# ProProject_PetCareSTM32_MiniSTM32_2024-0.net
KiCad netlist of a schematic drawn in EasyEDA Pro
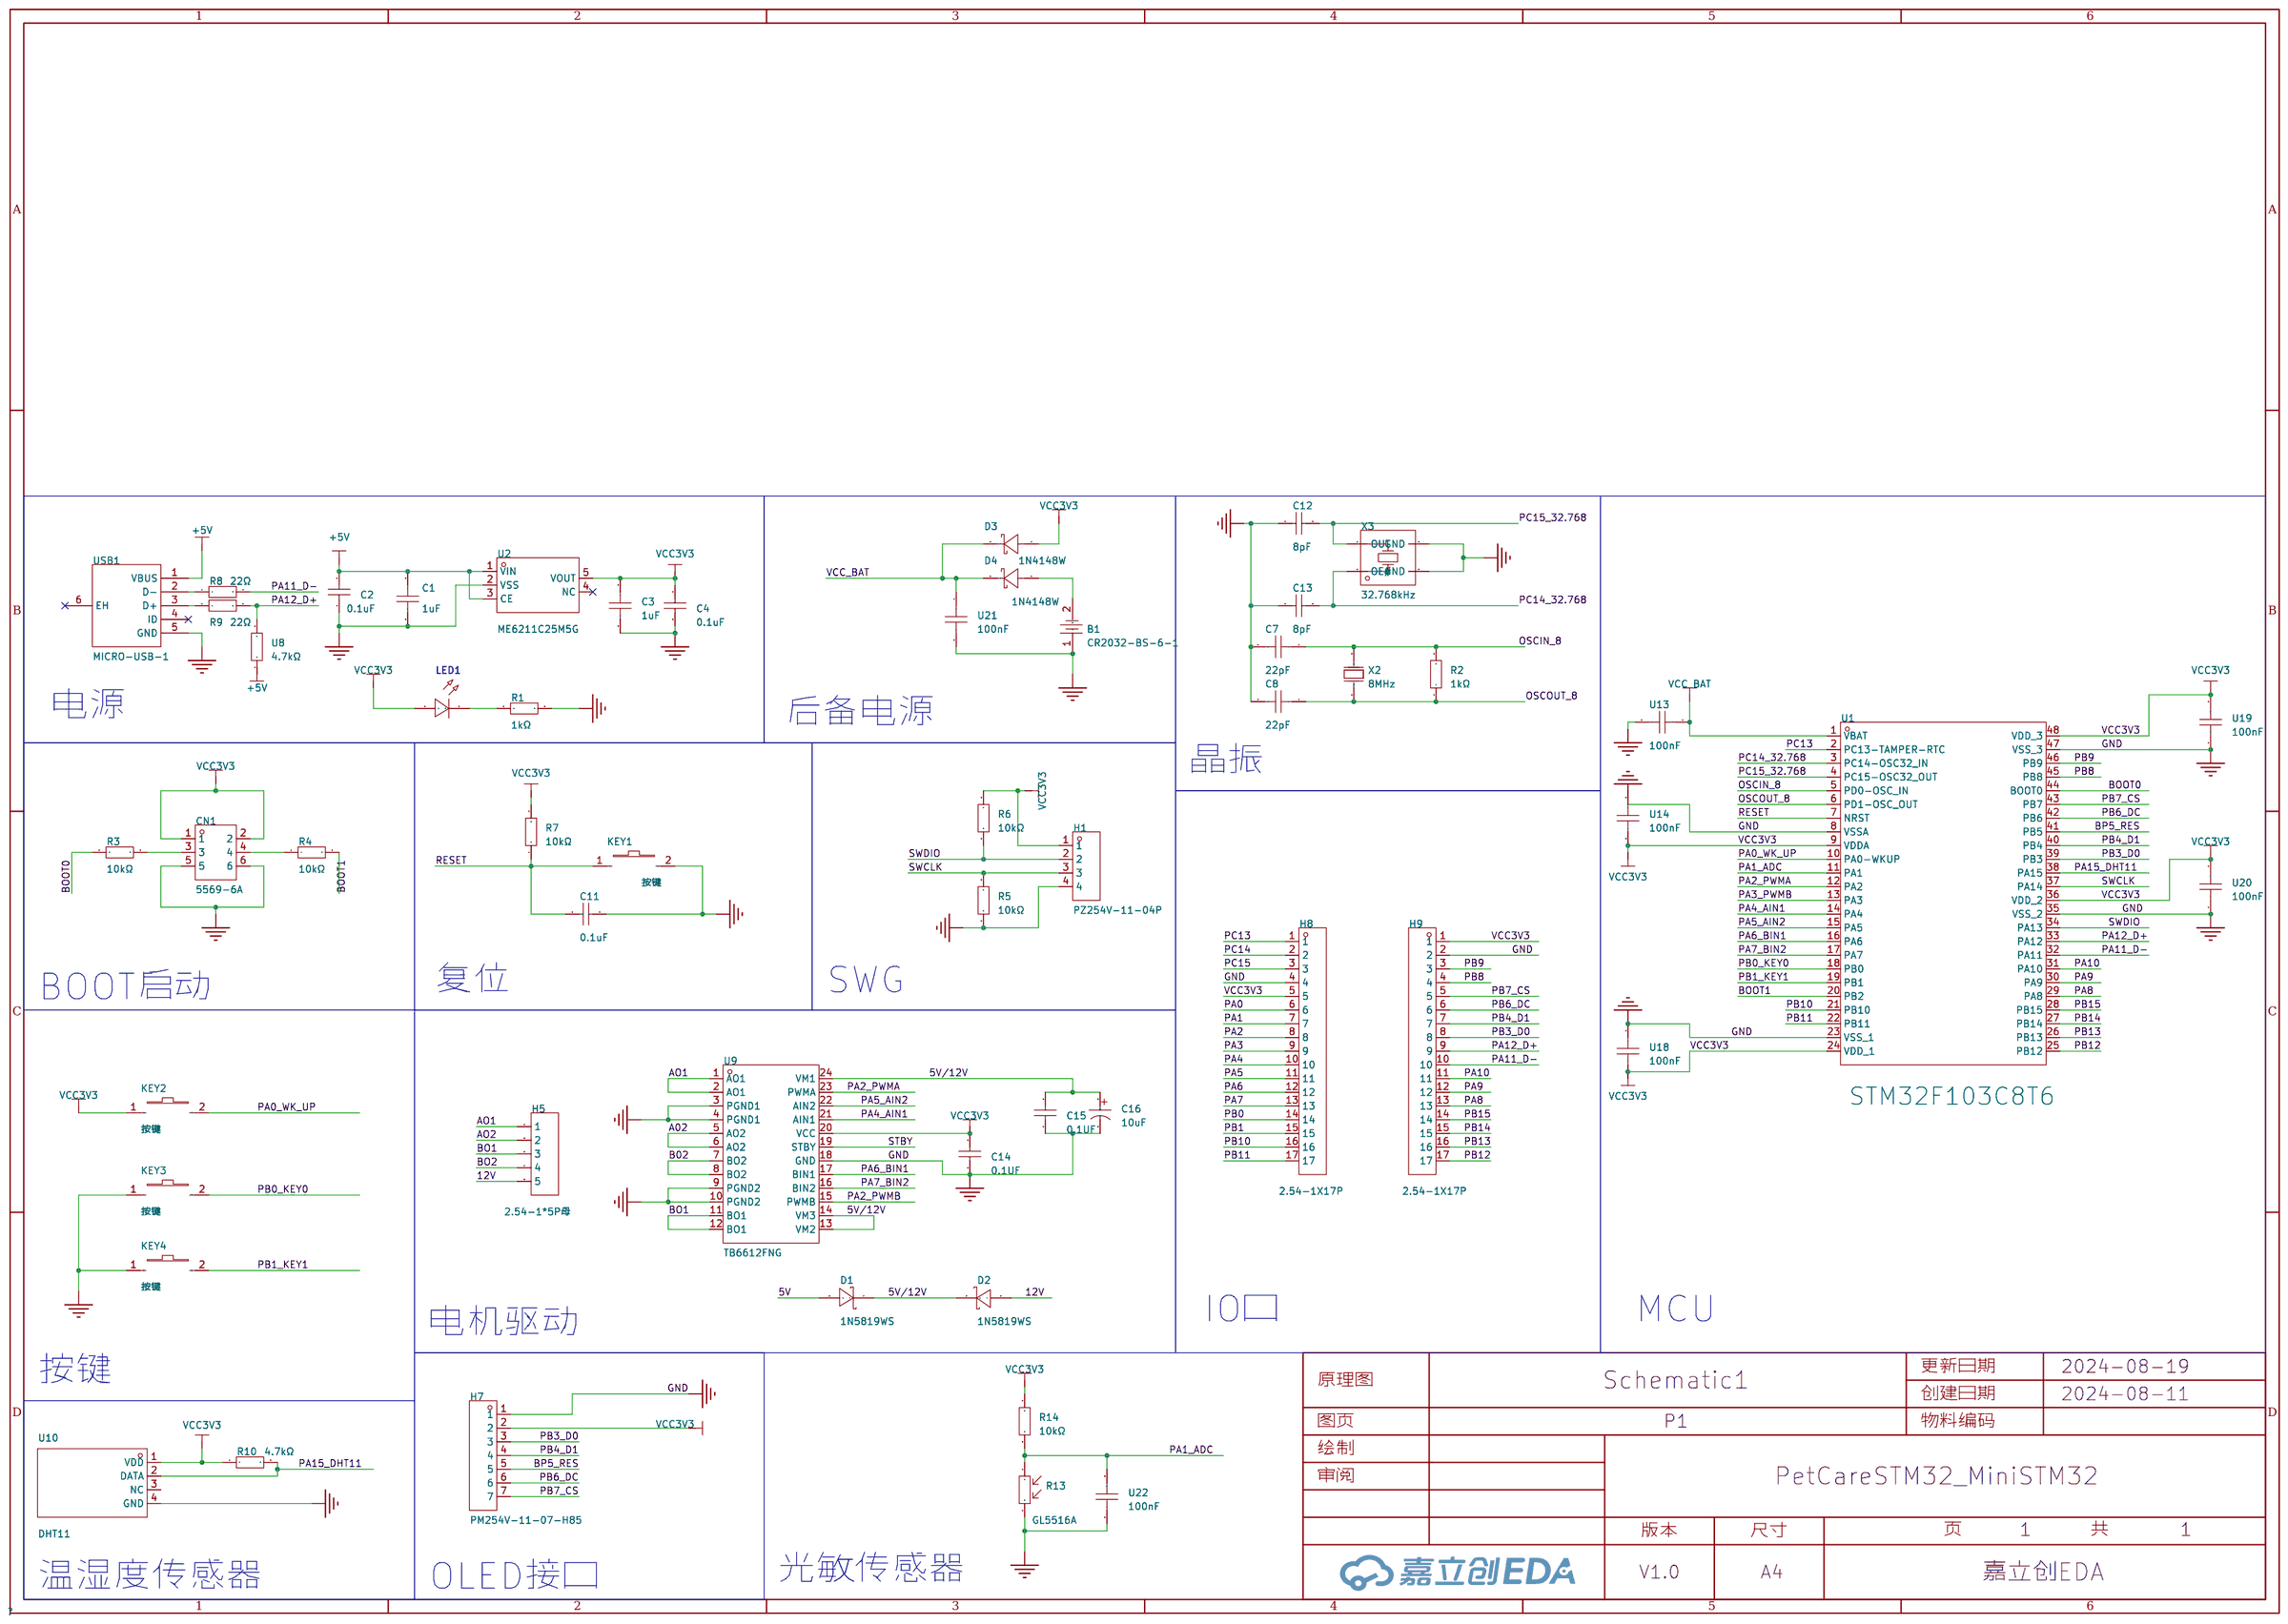
[diagram p0: schematic sheet]

(export (version "E")
  (design (tool "Eeschema 10.0.6"))
  (components
    (comp (ref "B1")
      (value "CR2032-BS-6-1")
      (footprint "easyedapro:BAT-TH_CR2032-BS-6-1")
      (description "连接器类型:电池底座;适用电池规格:CR2032;工作温度范围:-;")
      (fields (field (name "Manufacturer") "Q&J"))
      (libsource (lib "easyedapro") (part "CR2032-BS-6-1"))
    )
    (comp (ref "C1")
      (value "1uF")
      (footprint "easyedapro:C0603")
      (description "容值:1uF;精度:±10%;额定电压:50V;材质(温度系数):X5R;")
      (fields
        (field (name "Manufacturer Part") "CL10A105KB8NNNC")
        (field (name "Manufacturer") "SAMSUNG(三星)")
      )
      (libsource (lib "easyedapro") (part "CL10A105KB8NNNC"))
    )
    (comp (ref "C2")
      (value "0.1uF")
      (footprint "easyedapro:C0603")
      (libsource (lib "easyedapro") (part "CAPCER0.1UF16VX5R0603,CAPCER0.1UF25VX5R0603,CAPCER0.1UF16VX7R0603"))
    )
    (comp (ref "C3")
      (value "1uF")
      (footprint "easyedapro:C0603")
      (description "容值:1uF;精度:±10%;额定电压:50V;材质(温度系数):X5R;")
      (fields
        (field (name "Manufacturer Part") "CL10A105KB8NNNC")
        (field (name "Manufacturer") "SAMSUNG(三星)")
      )
      (libsource (lib "easyedapro") (part "CL10A105KB8NNNC"))
    )
    (comp (ref "C4")
      (value "0.1uF")
      (footprint "easyedapro:C0603")
      (libsource (lib "easyedapro") (part "CAPCER0.1UF16VX5R0603,CAPCER0.1UF25VX5R0603,CAPCER0.1UF16VX7R0603"))
    )
    (comp (ref "C7")
      (value "22pF")
      (footprint "easyedapro:C0603")
      (description "容值:22pF;精度:±5%;额定电压:50V;材质(温度系数):C0G;")
      (fields
        (field (name "Manufacturer Part") "CL10C220JB81PNC")
        (field (name "Manufacturer") "SAMSUNG(三星)")
      )
      (libsource (lib "easyedapro") (part "CL10C220JB81PNC"))
    )
    (comp (ref "C8")
      (value "22pF")
      (footprint "easyedapro:C0603")
      (description "容值:22pF;精度:±5%;额定电压:50V;材质(温度系数):C0G;")
      (fields
        (field (name "Manufacturer Part") "CL10C220JB81PNC")
        (field (name "Manufacturer") "SAMSUNG(三星)")
      )
      (libsource (lib "easyedapro") (part "CL10C220JB81PNC"))
    )
    (comp (ref "C11")
      (value "0.1uF")
      (footprint "easyedapro:C0603")
      (libsource (lib "easyedapro") (part "CAPCER0.1UF16VX5R0603,CAPCER0.1UF25VX5R0603,CAPCER0.1UF16VX7R0603"))
    )
    (comp (ref "C12")
      (value "8pF")
      (footprint "easyedapro:C0603")
      (description "容值:8pF;额定电压:50V;材质(温度系数):C0G;")
      (fields (field (name "Manufacturer Part") "0603CG8R0C500NT") (field (name "Manufacturer") "FH(风华)"))
      (libsource (lib "easyedapro") (part "0603CG8R0C500NT_C36508"))
    )
    (comp (ref "C13")
      (value "8pF")
      (footprint "easyedapro:C0603")
      (description "容值:8pF;额定电压:50V;材质(温度系数):C0G;")
      (fields (field (name "Manufacturer Part") "0603CG8R0C500NT") (field (name "Manufacturer") "FH(风华)"))
      (libsource (lib "easyedapro") (part "0603CG8R0C500NT_C36508"))
    )
    (comp (ref "C14")
      (value "0.1UF")
      (footprint "easyedapro:C0603")
      (libsource (lib "easyedapro") (part "CAPCER0.1UF16VX5R0603,CAPCER0.1UF25VX5R0603,CAPCER0.1UF16VX7R0603"))
    )
    (comp (ref "C15")
      (value "0.1UF")
      (footprint "easyedapro:C0603")
      (libsource (lib "easyedapro") (part "CAPCER0.1UF16VX5R0603,CAPCER0.1UF25VX5R0603,CAPCER0.1UF16VX7R0603"))
    )
    (comp (ref "C16")
      (value "10uF")
      (footprint "easyedapro:CAP-TH_BD5.0-P2.00-D0.8-FD")
      (description "容值:10uF;精度:±20%;额定电压:25V;")
      (fields (field (name "Manufacturer Part") "KF100M025C110A") (field (name "Manufacturer") "CapXon(丰宾)"))
      (libsource (lib "easyedapro") (part "KF100M025C110A"))
    )
    (comp (ref "CN1")
      (value "5569-6A")
      (footprint "easyedapro:CONN-TH_6P-P4.20_5569-6A-1")
      (libsource (lib "easyedapro") (part "5569-6A"))
    )
    (comp (ref "D1")
      (value "1N5819WS")
      (footprint "easyedapro:SOD-323_L1.8-W1.3-LS2.5-RD")
      (description "正向压降(Vf):600mV@1A;直流反向耐压(Vr):40V;平均整流电流(Io):1A;")
      (fields (field (name "Manufacturer") "Hottech(合科泰)"))
      (libsource (lib "easyedapro") (part "1N5819WS"))
    )
    (comp (ref "D2")
      (value "1N5819WS")
      (footprint "easyedapro:SOD-323_L1.8-W1.3-LS2.5-RD")
      (description "正向压降(Vf):600mV@1A;直流反向耐压(Vr):40V;平均整流电流(Io):1A;")
      (fields (field (name "Manufacturer") "Hottech(合科泰)"))
      (libsource (lib "easyedapro") (part "1N5819WS"))
    )
    (comp (ref "D3")
      (value "1N4148W")
      (footprint "easyedapro:SOD-123_L2.7-W1.6-LS3.7-FD")
      (description "二极管配置:独立式;正向压降(Vf):1.25V@150mA;直流反向耐压(Vr):100V;平均整流电流(Io):150mA;功率:400mW;反向恢复时间(trr):4ns;")
      (fields (field (name "Manufacturer") "宏迦橙"))
      (libsource (lib "easyedapro") (part "1N4148W_C7420318"))
    )
    (comp (ref "D4")
      (value "1N4148W")
      (footprint "easyedapro:SOD-123_L2.7-W1.6-LS3.7-FD")
      (description "二极管配置:独立式;正向压降(Vf):1.25V@150mA;直流反向耐压(Vr):100V;平均整流电流(Io):150mA;功率:400mW;反向恢复时间(trr):4ns;")
      (fields (field (name "Manufacturer") "宏迦橙"))
      (libsource (lib "easyedapro") (part "1N4148W_C7420318"))
    )
    (comp (ref "H1")
      (value "PZ254V-11-04P")
      (footprint "easyedapro:HDR-TH_4P-P2.54-V-M")
      (fields (field (name "Manufacturer") "XFCN(兴飞)"))
      (libsource (lib "easyedapro") (part "PZ254V-11-04P_C2691448"))
    )
    (comp (ref "H5")
      (value "2.54-1*5P母")
      (footprint "easyedapro:HDR-TH_5P-P2.54-V-F")
      (description "插孔结构:1x5P;间距:2.54mm;行距:-;安装类型:直插;排数:单排;总孔位数:5P;塑高:-;触头材质:-;触头镀层:-;")
      (fields (field (name "Manufacturer") "BOOMELE(博穆精密)"))
      (libsource (lib "easyedapro") (part "Header-Female-2.54_1x5"))
    )
    (comp (ref "H7")
      (value "PM254V-11-07-H85")
      (footprint "easyedapro:HDR-TH_7P-P2.54-V-F")
      (fields (field (name "Manufacturer") "XFCN(兴飞)"))
      (libsource (lib "easyedapro") (part "PM254V-11-07-H85"))
    )
    (comp (ref "H8")
      (value "2.54-1X17P")
      (footprint "easyedapro:HDR-TH_17P-P2.54-V-M")
      (fields (field (name "Manufacturer") "kinghelm(金航标)"))
      (libsource (lib "easyedapro") (part "KH-2.54PH180-1X17P-L11.5"))
    )
    (comp (ref "H9")
      (value "2.54-1X17P")
      (footprint "easyedapro:HDR-TH_17P-P2.54-V-M")
      (fields (field (name "Manufacturer") "kinghelm(金航标)"))
      (libsource (lib "easyedapro") (part "KH-2.54PH180-1X17P-L11.5"))
    )
    (comp (ref "KEY1")
      (value "按键")
      (footprint "easyedapro:SW-SMD_L6.0-W3.6-LS8.0")
      (libsource (lib "easyedapro") (part "3x6x2.5mm"))
    )
    (comp (ref "KEY2")
      (value "按键")
      (footprint "easyedapro:SW-SMD_L6.0-W3.6-LS8.0")
      (libsource (lib "easyedapro") (part "3x6x2.5mm"))
    )
    (comp (ref "KEY3")
      (value "按键")
      (footprint "easyedapro:SW-SMD_L6.0-W3.6-LS8.0")
      (libsource (lib "easyedapro") (part "3x6x2.5mm"))
    )
    (comp (ref "KEY4")
      (value "按键")
      (footprint "easyedapro:SW-SMD_L6.0-W3.6-LS8.0")
      (libsource (lib "easyedapro") (part "3x6x2.5mm"))
    )
    (comp (ref "LED1")
      (value "~")
      (footprint "easyedapro:LED_0805")
      (libsource (lib "easyedapro") (part "LED_B"))
    )
    (comp (ref "R1")
      (value "1kΩ")
      (footprint "easyedapro:R0603")
      (description "电阻类型:厚膜电阻;阻值:1kΩ;精度:±1%;功率:100mW;最大工作电压:75V;温度系数:±100ppm/°C;")
      (fields (field (name "Manufacturer Part") "RC0603FR-071KL") (field (name "Manufacturer") "YAGEO(国巨)"))
      (libsource (lib "easyedapro") (part "RC0603FR-071KL"))
    )
    (comp (ref "R2")
      (value "1kΩ")
      (footprint "easyedapro:R0603")
      (description "电阻类型:厚膜电阻;阻值:1kΩ;精度:±0.5%;功率:100mW;最大工作电压:75V;温度系数:±100ppm/°C;")
      (fields
        (field (name "Manufacturer Part") "0603WAD1001T5E")
        (field (name "Manufacturer") "UNI-ROYAL(厚声)")
      )
      (libsource (lib "easyedapro") (part "0603WAD1001T5E"))
    )
    (comp (ref "R3")
      (value "10kΩ")
      (footprint "easyedapro:R0603")
      (description "电阻类型:厚膜电阻;阻值:10kΩ;精度:±1%;功率:100mW;最大工作电压:75V;温度系数:±100ppm/°C;")
      (fields
        (field (name "Manufacturer Part") "0603WAF1002T5E")
        (field (name "Manufacturer") "UNI-ROYAL(厚声)")
      )
      (libsource (lib "easyedapro") (part "0603WAF1002T5E"))
    )
    (comp (ref "R4")
      (value "10kΩ")
      (footprint "easyedapro:R0603")
      (description "电阻类型:厚膜电阻;阻值:10kΩ;精度:±1%;功率:100mW;最大工作电压:75V;温度系数:±100ppm/°C;")
      (fields
        (field (name "Manufacturer Part") "0603WAF1002T5E")
        (field (name "Manufacturer") "UNI-ROYAL(厚声)")
      )
      (libsource (lib "easyedapro") (part "0603WAF1002T5E"))
    )
    (comp (ref "R5")
      (value "10kΩ")
      (footprint "easyedapro:R0603")
      (description "电阻类型:厚膜电阻;阻值:10kΩ;精度:±1%;功率:100mW;最大工作电压:75V;温度系数:±100ppm/°C;")
      (fields
        (field (name "Manufacturer Part") "0603WAF1002T5E")
        (field (name "Manufacturer") "UNI-ROYAL(厚声)")
      )
      (libsource (lib "easyedapro") (part "0603WAF1002T5E"))
    )
    (comp (ref "R6")
      (value "10kΩ")
      (footprint "easyedapro:R0603")
      (description "电阻类型:厚膜电阻;阻值:10kΩ;精度:±1%;功率:100mW;最大工作电压:75V;温度系数:±100ppm/°C;")
      (fields
        (field (name "Manufacturer Part") "0603WAF1002T5E")
        (field (name "Manufacturer") "UNI-ROYAL(厚声)")
      )
      (libsource (lib "easyedapro") (part "0603WAF1002T5E"))
    )
    (comp (ref "R7")
      (value "10kΩ")
      (footprint "easyedapro:R0603")
      (description "电阻类型:厚膜电阻;阻值:10kΩ;精度:±1%;功率:100mW;最大工作电压:75V;温度系数:±100ppm/°C;")
      (fields
        (field (name "Manufacturer Part") "0603WAF1002T5E")
        (field (name "Manufacturer") "UNI-ROYAL(厚声)")
      )
      (libsource (lib "easyedapro") (part "0603WAF1002T5E"))
    )
    (comp (ref "R8")
      (value "22Ω")
      (footprint "easyedapro:R0805")
      (description "电阻类型:薄膜电阻;阻值:22Ω;精度:±1%;功率:250mW;最大工作电压:150V;温度系数:±25ppm/°C;")
      (fields
        (field (name "Manufacturer Part") "TC0525F220JT5E")
        (field (name "Manufacturer") "UNI-ROYAL(厚声)")
      )
      (libsource (lib "easyedapro") (part "TC0525F220JT5E"))
    )
    (comp (ref "R9")
      (value "22Ω")
      (footprint "easyedapro:R0805")
      (description "电阻类型:薄膜电阻;阻值:22Ω;精度:±1%;功率:250mW;最大工作电压:150V;温度系数:±25ppm/°C;")
      (fields
        (field (name "Manufacturer Part") "TC0525F220JT5E")
        (field (name "Manufacturer") "UNI-ROYAL(厚声)")
      )
      (libsource (lib "easyedapro") (part "TC0525F220JT5E"))
    )
    (comp (ref "R10")
      (value "4.7kΩ")
      (footprint "easyedapro:R1206")
      (description "电阻类型:厚膜电阻;阻值:4.7kΩ;精度:±1%;功率:250mW;最大工作电压:200V;温度系数:±100ppm/°C;")
      (fields
        (field (name "Manufacturer Part") "1206W4F4701T5E")
        (field (name "Manufacturer") "UNI-ROYAL(厚声)")
      )
      (libsource (lib "easyedapro") (part "1206W4F4701T5E"))
    )
    (comp (ref "R13")
      (value "GL5516A")
      (footprint "easyedapro:RES-TH_L5.1-W4.3-P3.40_GL55")
      (description "暗电阻:200kΩ;亮电阻 @ 10Lux:5kΩ~10kΩ;光谱峰值(波长):540nm;")
      (fields (field (name "Manufacturer") "JCHL(晶创和立)"))
      (libsource (lib "easyedapro") (part "GL5516A(5-10K)"))
    )
    (comp (ref "R14")
      (value "10kΩ")
      (footprint "easyedapro:R0603")
      (description "电阻类型:厚膜电阻;阻值:10kΩ;精度:±1%;功率:100mW;最大工作电压:75V;温度系数:±100ppm/°C;")
      (fields
        (field (name "Manufacturer Part") "0603WAF1002T5E")
        (field (name "Manufacturer") "UNI-ROYAL(厚声)")
      )
      (libsource (lib "easyedapro") (part "0603WAF1002T5E"))
    )
    (comp (ref "U1")
      (value "STM32F103C8T6")
      (footprint "easyedapro:LQFP-48_L7.0-W7.0-P0.50-LS9.0-BL")
      (description "CPU内核:ARM-M3;程序存储容量:64KB;RAM总容量:20KB;GPIO端口数量:37;工作电压范围:2V~3.6V;CPU最大主频:72MHz;程序存储器类型:FLASH;")
      (fields (field (name "Manufacturer") "ST(意法半导体)"))
      (libsource (lib "easyedapro") (part "STM32F103C8T6"))
    )
    (comp (ref "U2")
      (value "ME6211C25M5G")
      (footprint "easyedapro:SOT-23-5_L2.9-W1.7-P0.95-LS2.8-BL")
      (fields (field (name "Manufacturer") "MICRONE(南京微盟)"))
      (libsource (lib "easyedapro") (part "ME6211C25M5G"))
    )
    (comp (ref "U8")
      (value "4.7kΩ")
      (footprint "easyedapro:R0603")
      (description "电阻类型:薄膜电阻;阻值:4.7kΩ;精度:±1%;功率:100mW;最大工作电压:75V;温度系数:±50ppm/°C;")
      (fields (field (name "Manufacturer Part") "AR03FTDX4701A") (field (name "Manufacturer") "Viking(光颉)"))
      (libsource (lib "easyedapro") (part "AR03FTDX4701A"))
    )
    (comp (ref "U9")
      (value "TB6612FNG")
      (footprint "easyedapro:SSOP-24_L8.4-W5.8-P0.65-LS7.8-BL")
      (description "双直流电机驱动器集成电路")
      (fields (field (name "Manufacturer") "TOSHIBA(东芝)"))
      (libsource (lib "easyedapro") (part "TB6612FNG(O,C,8,EL"))
    )
    (comp (ref "U10")
      (value "DHT11")
      (footprint "easyedapro:SENSOR-TH_DHT11")
      (description "新款电容式数字温湿度传感器,老款已停产16.1x12.6x5.8mm")
      (fields (field (name "Manufacturer") "广州奥松"))
      (libsource (lib "easyedapro") (part "DHT11"))
    )
    (comp (ref "U13")
      (value "100nF")
      (footprint "easyedapro:C0603")
      (description "容值:100nF;精度:±10%;额定电压:50V;材质(温度系数):X7R;")
      (fields
        (field (name "Manufacturer Part") "CGA0603X7R104K500JT")
        (field (name "Manufacturer") "HRE(芯声)")
      )
      (libsource (lib "easyedapro") (part "CGA0603X7R104K500JT"))
    )
    (comp (ref "U14")
      (value "100nF")
      (footprint "easyedapro:C0603")
      (description "容值:100nF;精度:±10%;额定电压:50V;材质(温度系数):X7R;")
      (fields
        (field (name "Manufacturer Part") "CGA0603X7R104K500JT")
        (field (name "Manufacturer") "HRE(芯声)")
      )
      (libsource (lib "easyedapro") (part "CGA0603X7R104K500JT"))
    )
    (comp (ref "U18")
      (value "100nF")
      (footprint "easyedapro:C0603")
      (description "容值:100nF;精度:±10%;额定电压:50V;材质(温度系数):X7R;")
      (fields
        (field (name "Manufacturer Part") "CGA0603X7R104K500JT")
        (field (name "Manufacturer") "HRE(芯声)")
      )
      (libsource (lib "easyedapro") (part "CGA0603X7R104K500JT"))
    )
    (comp (ref "U19")
      (value "100nF")
      (footprint "easyedapro:C0603")
      (description "容值:100nF;精度:±10%;额定电压:50V;材质(温度系数):X7R;")
      (fields
        (field (name "Manufacturer Part") "CGA0603X7R104K500JT")
        (field (name "Manufacturer") "HRE(芯声)")
      )
      (libsource (lib "easyedapro") (part "CGA0603X7R104K500JT"))
    )
    (comp (ref "U20")
      (value "100nF")
      (footprint "easyedapro:C0603")
      (description "容值:100nF;精度:±10%;额定电压:50V;材质(温度系数):X7R;")
      (fields
        (field (name "Manufacturer Part") "CGA0603X7R104K500JT")
        (field (name "Manufacturer") "HRE(芯声)")
      )
      (libsource (lib "easyedapro") (part "CGA0603X7R104K500JT"))
    )
    (comp (ref "U21")
      (value "100nF")
      (footprint "easyedapro:C0603")
      (description "容值:100nF;精度:±10%;额定电压:50V;材质(温度系数):X7R;")
      (fields
        (field (name "Manufacturer Part") "CGA0603X7R104K500JT")
        (field (name "Manufacturer") "HRE(芯声)")
      )
      (libsource (lib "easyedapro") (part "CGA0603X7R104K500JT"))
    )
    (comp (ref "U22")
      (value "100nF")
      (footprint "easyedapro:C0603")
      (description "容值:100nF;精度:±10%;额定电压:50V;材质(温度系数):X7R;")
      (fields
        (field (name "Manufacturer Part") "CGA0603X7R104K500JT")
        (field (name "Manufacturer") "HRE(芯声)")
      )
      (libsource (lib "easyedapro") (part "CGA0603X7R104K500JT"))
    )
    (comp (ref "USB1")
      (value "MICRO-USB-1")
      (footprint "easyedapro:MICRO-USB-SMD_C9900008946")
      (libsource (lib "easyedapro") (part "MICRO-USB-1"))
    )
    (comp (ref "X2")
      (value "8MHz")
      (footprint "easyedapro:OSC-SMD_L5.0-W3.2")
      (description "晶振类型:贴片晶振;频率:8MHz;常温频差:±20ppm;外接负载电容:18pF;频率稳定度(全温):±30ppm;")
      (fields
        (field (name "Manufacturer Part") "ABM3-8.000MHZ-D2Y-T")
        (field (name "Manufacturer") "ABRACON")
      )
      (libsource (lib "easyedapro") (part "ABM3-8.000MHZ-D2Y-T"))
    )
    (comp (ref "X3")
      (value "32.768kHz")
      (footprint "easyedapro:CRYSTAL-SMD_4P-L8.0-W3.8-BL")
      (description "晶振类型:-;频率:32.768kHz;常温频差:±20ppm;外接负载电容:12.5pF;频率稳定度(全温):-;")
      (fields (field (name "Manufacturer Part") "ABS25-32.768KHZ-T") (field (name "Manufacturer") "ABRACON"))
      (libsource (lib "easyedapro") (part "ABS25-32.768KHZ-T"))
    )
  )
  (nets
    (net (code "1") (name "+5V") (class "Default")
      (node (ref "C1") (pin "2") (pinfunction "2_2") (pintype "unspecified"))
      (node (ref "C2") (pin "2") (pinfunction "2_2") (pintype "input"))
      (node (ref "U2") (pin "1") (pinfunction "VIN_1") (pintype "unspecified"))
      (node (ref "U2") (pin "3") (pinfunction "CE_3") (pintype "unspecified"))
      (node (ref "U8") (pin "1") (pinfunction "1_1") (pintype "unspecified"))
      (node (ref "USB1") (pin "1") (pinfunction "VBUS_1") (pintype "input"))
    )
    (net (code "2") (name "/5V") (class "Default")
      (node (ref "D1") (pin "2") (pinfunction "A_2") (pintype "unspecified"))
    )
    (net (code "3") (name "/5V{slash}12V") (class "Default")
      (node (ref "C15") (pin "2") (pinfunction "2_2") (pintype "input"))
      (node (ref "C16") (pin "1") (pinfunction "1_1") (pintype "input"))
      (node (ref "D1") (pin "1") (pinfunction "K_1") (pintype "unspecified"))
      (node (ref "D2") (pin "1") (pinfunction "K_1") (pintype "unspecified"))
      (node (ref "U9") (pin "13") (pinfunction "VM2_13") (pintype "unspecified"))
      (node (ref "U9") (pin "14") (pinfunction "VM3_14") (pintype "unspecified"))
      (node (ref "U9") (pin "24") (pinfunction "VM1_24") (pintype "unspecified"))
    )
    (net (code "4") (name "/12V") (class "Default")
      (node (ref "D2") (pin "2") (pinfunction "A_2") (pintype "unspecified"))
      (node (ref "H5") (pin "5") (pinfunction "5_5") (pintype "input"))
    )
    (net (code "5") (name "/A02") (class "Default")
      (node (ref "U9") (pin "5") (pinfunction "AO2_5") (pintype "unspecified"))
      (node (ref "U9") (pin "6") (pinfunction "AO2_6") (pintype "unspecified"))
    )
    (net (code "6") (name "/AO1") (class "Default")
      (node (ref "H5") (pin "1") (pinfunction "1_1") (pintype "input"))
      (node (ref "U9") (pin "1") (pinfunction "AO1_1") (pintype "unspecified"))
      (node (ref "U9") (pin "2") (pinfunction "AO1_2") (pintype "unspecified"))
    )
    (net (code "7") (name "/AO2") (class "Default")
      (node (ref "H5") (pin "2") (pinfunction "2_2") (pintype "input"))
    )
    (net (code "8") (name "/B02") (class "Default")
      (node (ref "U9") (pin "7") (pinfunction "BO2_7") (pintype "unspecified"))
      (node (ref "U9") (pin "8") (pinfunction "BO2_8") (pintype "unspecified"))
    )
    (net (code "9") (name "/BO1") (class "Default")
      (node (ref "H5") (pin "3") (pinfunction "3_3") (pintype "input"))
      (node (ref "U9") (pin "11") (pinfunction "BO1_11") (pintype "unspecified"))
      (node (ref "U9") (pin "12") (pinfunction "BO1_12") (pintype "unspecified"))
    )
    (net (code "10") (name "/BO2") (class "Default")
      (node (ref "H5") (pin "4") (pinfunction "4_4") (pintype "input"))
    )
    (net (code "11") (name "/BOOT0") (class "Default")
      (node (ref "R3") (pin "1") (pinfunction "1_1") (pintype "input"))
      (node (ref "U1") (pin "44") (pinfunction "BOOT0_44") (pintype "unspecified"))
    )
    (net (code "12") (name "/BOOT1") (class "Default")
      (node (ref "R4") (pin "2") (pinfunction "2_2") (pintype "input"))
      (node (ref "U1") (pin "20") (pinfunction "PB2_20") (pintype "unspecified"))
    )
    (net (code "13") (name "/BP5_RES") (class "Default")
      (node (ref "H7") (pin "5") (pinfunction "5_5") (pintype "unspecified"))
      (node (ref "U1") (pin "41") (pinfunction "PB5_41") (pintype "unspecified"))
    )
    (net (code "14") (name "/OSCIN_8") (class "Default")
      (node (ref "C7") (pin "1") (pinfunction "1_1") (pintype "unspecified"))
      (node (ref "R2") (pin "2") (pinfunction "2_2") (pintype "input"))
      (node (ref "U1") (pin "5") (pinfunction "PD0-OSC_IN_5") (pintype "unspecified"))
      (node (ref "X2") (pin "2") (pinfunction "OSC2_2") (pintype "input"))
    )
    (net (code "15") (name "/OSCOUT_8") (class "Default")
      (node (ref "C8") (pin "1") (pinfunction "1_1") (pintype "unspecified"))
      (node (ref "R2") (pin "1") (pinfunction "1_1") (pintype "input"))
      (node (ref "U1") (pin "6") (pinfunction "PD1-OSC_OUT_6") (pintype "unspecified"))
      (node (ref "X2") (pin "1") (pinfunction "OSC1_1") (pintype "input"))
    )
    (net (code "16") (name "/PA0") (class "Default")
      (node (ref "H8") (pin "6") (pinfunction "6_6") (pintype "unspecified"))
    )
    (net (code "17") (name "/PA0_WK_UP") (class "Default")
      (node (ref "KEY2") (pin "2") (pinfunction "2_2") (pintype "input"))
      (node (ref "U1") (pin "10") (pinfunction "PA0-WKUP_10") (pintype "unspecified"))
    )
    (net (code "18") (name "/PA1") (class "Default")
      (node (ref "H8") (pin "7") (pinfunction "7_7") (pintype "unspecified"))
    )
    (net (code "19") (name "/PA1_ADC") (class "Default")
      (node (ref "R13") (pin "1") (pinfunction "1_1") (pintype "input"))
      (node (ref "R14") (pin "1") (pinfunction "1_1") (pintype "input"))
      (node (ref "U1") (pin "11") (pinfunction "PA1_11") (pintype "unspecified"))
      (node (ref "U22") (pin "2") (pinfunction "2_2") (pintype "unspecified"))
    )
    (net (code "20") (name "/PA2") (class "Default")
      (node (ref "H8") (pin "8") (pinfunction "8_8") (pintype "unspecified"))
    )
    (net (code "21") (name "/PA2_PWMA") (class "Default")
      (node (ref "U1") (pin "12") (pinfunction "PA2_12") (pintype "unspecified"))
      (node (ref "U9") (pin "23") (pinfunction "PWMA_23") (pintype "unspecified"))
    )
    (net (code "22") (name "/PA2_PWMB") (class "Default")
      (node (ref "U9") (pin "15") (pinfunction "PWMB_15") (pintype "unspecified"))
    )
    (net (code "23") (name "/PA3") (class "Default")
      (node (ref "H8") (pin "9") (pinfunction "9_9") (pintype "unspecified"))
    )
    (net (code "24") (name "/PA3_PWMB") (class "Default")
      (node (ref "U1") (pin "13") (pinfunction "PA3_13") (pintype "unspecified"))
    )
    (net (code "25") (name "/PA4") (class "Default")
      (node (ref "H8") (pin "10") (pinfunction "10_10") (pintype "unspecified"))
    )
    (net (code "26") (name "/PA4_AIN1") (class "Default")
      (node (ref "U1") (pin "14") (pinfunction "PA4_14") (pintype "unspecified"))
      (node (ref "U9") (pin "21") (pinfunction "AIN1_21") (pintype "unspecified"))
    )
    (net (code "27") (name "/PA5") (class "Default")
      (node (ref "H8") (pin "11") (pinfunction "11_11") (pintype "unspecified"))
    )
    (net (code "28") (name "/PA5_AIN2") (class "Default")
      (node (ref "U1") (pin "15") (pinfunction "PA5_15") (pintype "unspecified"))
      (node (ref "U9") (pin "22") (pinfunction "AIN2_22") (pintype "unspecified"))
    )
    (net (code "29") (name "/PA6") (class "Default")
      (node (ref "H8") (pin "12") (pinfunction "12_12") (pintype "unspecified"))
    )
    (net (code "30") (name "/PA6_BIN1") (class "Default")
      (node (ref "U1") (pin "16") (pinfunction "PA6_16") (pintype "unspecified"))
      (node (ref "U9") (pin "17") (pinfunction "BIN1_17") (pintype "unspecified"))
    )
    (net (code "31") (name "/PA7") (class "Default")
      (node (ref "H8") (pin "13") (pinfunction "13_13") (pintype "unspecified"))
    )
    (net (code "32") (name "/PA7_BIN2") (class "Default")
      (node (ref "U1") (pin "17") (pinfunction "PA7_17") (pintype "unspecified"))
      (node (ref "U9") (pin "16") (pinfunction "BIN2_16") (pintype "unspecified"))
    )
    (net (code "33") (name "/PA8") (class "Default")
      (node (ref "H9") (pin "13") (pinfunction "13_13") (pintype "unspecified"))
      (node (ref "U1") (pin "29") (pinfunction "PA8_29") (pintype "unspecified"))
    )
    (net (code "34") (name "/PA9") (class "Default")
      (node (ref "H9") (pin "12") (pinfunction "12_12") (pintype "unspecified"))
      (node (ref "U1") (pin "30") (pinfunction "PA9_30") (pintype "unspecified"))
    )
    (net (code "35") (name "/PA10") (class "Default")
      (node (ref "H9") (pin "11") (pinfunction "11_11") (pintype "unspecified"))
      (node (ref "U1") (pin "31") (pinfunction "PA10_31") (pintype "unspecified"))
    )
    (net (code "36") (name "/PA11_D-") (class "Default")
      (node (ref "H9") (pin "10") (pinfunction "10_10") (pintype "unspecified"))
      (node (ref "R8") (pin "2") (pinfunction "2_2") (pintype "input"))
      (node (ref "U1") (pin "32") (pinfunction "PA11_32") (pintype "unspecified"))
    )
    (net (code "37") (name "/PA12_D+") (class "Default")
      (node (ref "H9") (pin "9") (pinfunction "9_9") (pintype "unspecified"))
      (node (ref "R9") (pin "2") (pinfunction "2_2") (pintype "input"))
      (node (ref "U1") (pin "33") (pinfunction "PA12_33") (pintype "unspecified"))
      (node (ref "U8") (pin "2") (pinfunction "2_2") (pintype "unspecified"))
    )
    (net (code "38") (name "/PA15_DHT11") (class "Default")
      (node (ref "R10") (pin "2") (pinfunction "2_2") (pintype "input"))
      (node (ref "U1") (pin "38") (pinfunction "PA15_38") (pintype "unspecified"))
      (node (ref "U10") (pin "2") (pinfunction "DATA_2") (pintype "unspecified"))
    )
    (net (code "39") (name "/PB0") (class "Default")
      (node (ref "H8") (pin "14") (pinfunction "14_14") (pintype "unspecified"))
    )
    (net (code "40") (name "/PB0_KEY0") (class "Default")
      (node (ref "KEY3") (pin "2") (pinfunction "2_2") (pintype "input"))
      (node (ref "U1") (pin "18") (pinfunction "PB0_18") (pintype "unspecified"))
    )
    (net (code "41") (name "/PB1") (class "Default")
      (node (ref "H8") (pin "15") (pinfunction "15_15") (pintype "unspecified"))
    )
    (net (code "42") (name "/PB1_KEY1") (class "Default")
      (node (ref "KEY4") (pin "2") (pinfunction "2_2") (pintype "input"))
      (node (ref "U1") (pin "19") (pinfunction "PB1_19") (pintype "unspecified"))
    )
    (net (code "43") (name "/PB3_D0") (class "Default")
      (node (ref "H7") (pin "3") (pinfunction "3_3") (pintype "unspecified"))
      (node (ref "H9") (pin "8") (pinfunction "8_8") (pintype "unspecified"))
      (node (ref "U1") (pin "39") (pinfunction "PB3_39") (pintype "unspecified"))
    )
    (net (code "44") (name "/PB4_D1") (class "Default")
      (node (ref "H7") (pin "4") (pinfunction "4_4") (pintype "unspecified"))
      (node (ref "H9") (pin "7") (pinfunction "7_7") (pintype "unspecified"))
      (node (ref "U1") (pin "40") (pinfunction "PB4_40") (pintype "unspecified"))
    )
    (net (code "45") (name "/PB6_DC") (class "Default")
      (node (ref "H7") (pin "6") (pinfunction "6_6") (pintype "unspecified"))
      (node (ref "H9") (pin "6") (pinfunction "6_6") (pintype "unspecified"))
      (node (ref "U1") (pin "42") (pinfunction "PB6_42") (pintype "unspecified"))
    )
    (net (code "46") (name "/PB7_CS") (class "Default")
      (node (ref "H7") (pin "7") (pinfunction "7_7") (pintype "unspecified"))
      (node (ref "H9") (pin "5") (pinfunction "5_5") (pintype "unspecified"))
      (node (ref "U1") (pin "43") (pinfunction "PB7_43") (pintype "unspecified"))
    )
    (net (code "47") (name "/PB8") (class "Default")
      (node (ref "H9") (pin "4") (pinfunction "4_4") (pintype "unspecified"))
      (node (ref "U1") (pin "45") (pinfunction "PB8_45") (pintype "unspecified"))
    )
    (net (code "48") (name "/PB9") (class "Default")
      (node (ref "H9") (pin "3") (pinfunction "3_3") (pintype "unspecified"))
      (node (ref "U1") (pin "46") (pinfunction "PB9_46") (pintype "unspecified"))
    )
    (net (code "49") (name "/PB10") (class "Default")
      (node (ref "H8") (pin "16") (pinfunction "16_16") (pintype "unspecified"))
      (node (ref "U1") (pin "21") (pinfunction "PB10_21") (pintype "unspecified"))
    )
    (net (code "50") (name "/PB11") (class "Default")
      (node (ref "H8") (pin "17") (pinfunction "17_17") (pintype "unspecified"))
      (node (ref "U1") (pin "22") (pinfunction "PB11_22") (pintype "unspecified"))
    )
    (net (code "51") (name "/PB12") (class "Default")
      (node (ref "H9") (pin "17") (pinfunction "17_17") (pintype "unspecified"))
      (node (ref "U1") (pin "25") (pinfunction "PB12_25") (pintype "unspecified"))
    )
    (net (code "52") (name "/PB13") (class "Default")
      (node (ref "H9") (pin "16") (pinfunction "16_16") (pintype "unspecified"))
      (node (ref "U1") (pin "26") (pinfunction "PB13_26") (pintype "unspecified"))
    )
    (net (code "53") (name "/PB14") (class "Default")
      (node (ref "H9") (pin "15") (pinfunction "15_15") (pintype "unspecified"))
      (node (ref "U1") (pin "27") (pinfunction "PB14_27") (pintype "unspecified"))
    )
    (net (code "54") (name "/PB15") (class "Default")
      (node (ref "H9") (pin "14") (pinfunction "14_14") (pintype "unspecified"))
      (node (ref "U1") (pin "28") (pinfunction "PB15_28") (pintype "unspecified"))
    )
    (net (code "55") (name "/PC13") (class "Default")
      (node (ref "H8") (pin "1") (pinfunction "1_1") (pintype "unspecified"))
      (node (ref "U1") (pin "2") (pinfunction "PC13-TAMPER-RTC_2") (pintype "unspecified"))
    )
    (net (code "56") (name "/PC14") (class "Default")
      (node (ref "H8") (pin "2") (pinfunction "2_2") (pintype "unspecified"))
    )
    (net (code "57") (name "/PC14_32.768") (class "Default")
      (node (ref "C13") (pin "2") (pinfunction "2_2") (pintype "input"))
      (node (ref "U1") (pin "3") (pinfunction "PC14-OSC32_IN_3") (pintype "unspecified"))
      (node (ref "X3") (pin "1") (pinfunction "OE#_1") (pintype "input"))
    )
    (net (code "58") (name "/PC15") (class "Default")
      (node (ref "H8") (pin "3") (pinfunction "3_3") (pintype "unspecified"))
    )
    (net (code "59") (name "/PC15_32.768") (class "Default")
      (node (ref "C12") (pin "2") (pinfunction "2_2") (pintype "input"))
      (node (ref "U1") (pin "4") (pinfunction "PC15-OSC32_OUT_4") (pintype "unspecified"))
      (node (ref "X3") (pin "4") (pinfunction "OUT_4") (pintype "input"))
    )
    (net (code "60") (name "/RESET") (class "Default")
      (node (ref "C11") (pin "1") (pinfunction "1_1") (pintype "input"))
      (node (ref "KEY1") (pin "1") (pinfunction "1_1") (pintype "input"))
      (node (ref "R7") (pin "1") (pinfunction "1_1") (pintype "input"))
      (node (ref "U1") (pin "7") (pinfunction "NRST_7") (pintype "unspecified"))
    )
    (net (code "61") (name "/STBY") (class "Default")
      (node (ref "U9") (pin "19") (pinfunction "STBY_19") (pintype "unspecified"))
    )
    (net (code "62") (name "/SWCLK") (class "Default")
      (node (ref "H1") (pin "3") (pinfunction "3_3") (pintype "unspecified"))
      (node (ref "R5") (pin "2") (pinfunction "2_2") (pintype "input"))
      (node (ref "U1") (pin "37") (pinfunction "PA14_37") (pintype "unspecified"))
    )
    (net (code "63") (name "/SWDIO") (class "Default")
      (node (ref "H1") (pin "2") (pinfunction "2_2") (pintype "unspecified"))
      (node (ref "R6") (pin "1") (pinfunction "1_1") (pintype "input"))
      (node (ref "U1") (pin "34") (pinfunction "PA13_34") (pintype "unspecified"))
    )
    (net (code "64") (name "GND") (class "Default")
      (node (ref "B1") (pin "1") (pinfunction "1_1") (pintype "input"))
      (node (ref "C1") (pin "1") (pinfunction "1_1") (pintype "unspecified"))
      (node (ref "C11") (pin "2") (pinfunction "2_2") (pintype "input"))
      (node (ref "C12") (pin "1") (pinfunction "1_1") (pintype "input"))
      (node (ref "C13") (pin "1") (pinfunction "1_1") (pintype "input"))
      (node (ref "C14") (pin "1") (pinfunction "1_1") (pintype "input"))
      (node (ref "C15") (pin "1") (pinfunction "1_1") (pintype "input"))
      (node (ref "C16") (pin "2") (pinfunction "2_2") (pintype "input"))
      (node (ref "C2") (pin "1") (pinfunction "1_1") (pintype "input"))
      (node (ref "C3") (pin "1") (pinfunction "1_1") (pintype "unspecified"))
      (node (ref "C4") (pin "1") (pinfunction "1_1") (pintype "input"))
      (node (ref "C7") (pin "2") (pinfunction "2_2") (pintype "unspecified"))
      (node (ref "C8") (pin "2") (pinfunction "2_2") (pintype "unspecified"))
      (node (ref "CN1") (pin "5") (pinfunction "5_5") (pintype "unspecified"))
      (node (ref "CN1") (pin "6") (pinfunction "6_6") (pintype "unspecified"))
      (node (ref "H1") (pin "4") (pinfunction "4_4") (pintype "unspecified"))
      (node (ref "H7") (pin "1") (pinfunction "1_1") (pintype "unspecified"))
      (node (ref "H8") (pin "4") (pinfunction "4_4") (pintype "unspecified"))
      (node (ref "H9") (pin "2") (pinfunction "2_2") (pintype "unspecified"))
      (node (ref "KEY1") (pin "2") (pinfunction "2_2") (pintype "input"))
      (node (ref "KEY3") (pin "1") (pinfunction "1_1") (pintype "input"))
      (node (ref "KEY4") (pin "1") (pinfunction "1_1") (pintype "input"))
      (node (ref "R1") (pin "2") (pinfunction "2_2") (pintype "input"))
      (node (ref "R13") (pin "2") (pinfunction "2_2") (pintype "input"))
      (node (ref "R5") (pin "1") (pinfunction "1_1") (pintype "input"))
      (node (ref "U1") (pin "23") (pinfunction "VSS_1_23") (pintype "unspecified"))
      (node (ref "U1") (pin "35") (pinfunction "VSS_2_35") (pintype "unspecified"))
      (node (ref "U1") (pin "47") (pinfunction "VSS_3_47") (pintype "unspecified"))
      (node (ref "U1") (pin "8") (pinfunction "VSSA_8") (pintype "unspecified"))
      (node (ref "U10") (pin "4") (pinfunction "GND_4") (pintype "unspecified"))
      (node (ref "U13") (pin "2") (pinfunction "2_2") (pintype "unspecified"))
      (node (ref "U14") (pin "2") (pinfunction "2_2") (pintype "unspecified"))
      (node (ref "U18") (pin "2") (pinfunction "2_2") (pintype "unspecified"))
      (node (ref "U19") (pin "1") (pinfunction "1_1") (pintype "unspecified"))
      (node (ref "U2") (pin "2") (pinfunction "VSS_2") (pintype "unspecified"))
      (node (ref "U20") (pin "1") (pinfunction "1_1") (pintype "unspecified"))
      (node (ref "U21") (pin "2") (pinfunction "2_2") (pintype "unspecified"))
      (node (ref "U22") (pin "1") (pinfunction "1_1") (pintype "unspecified"))
      (node (ref "U9") (pin "10") (pinfunction "PGND2_10") (pintype "unspecified"))
      (node (ref "U9") (pin "18") (pinfunction "GND_18") (pintype "unspecified"))
      (node (ref "U9") (pin "3") (pinfunction "PGND1_3") (pintype "unspecified"))
      (node (ref "U9") (pin "4") (pinfunction "PGND1_4") (pintype "unspecified"))
      (node (ref "U9") (pin "9") (pinfunction "PGND2_9") (pintype "unspecified"))
      (node (ref "USB1") (pin "5") (pinfunction "GND_5") (pintype "input"))
      (node (ref "X3") (pin "2") (pinfunction "GND_2") (pintype "input"))
      (node (ref "X3") (pin "3") (pinfunction "GND_3") (pintype "input"))
    )
    (net (code "65") (name "Net-(CN1-Pad3)") (class "Default")
      (node (ref "CN1") (pin "3") (pinfunction "3_3") (pintype "unspecified"))
      (node (ref "R3") (pin "2") (pinfunction "2_2") (pintype "input"))
    )
    (net (code "66") (name "Net-(CN1-Pad4)") (class "Default")
      (node (ref "CN1") (pin "4") (pinfunction "4_4") (pintype "unspecified"))
      (node (ref "R4") (pin "1") (pinfunction "1_1") (pintype "input"))
    )
    (net (code "67") (name "Net-(D4-A)") (class "Default")
      (node (ref "B1") (pin "2") (pinfunction "2_2") (pintype "input"))
      (node (ref "D4") (pin "1") (pinfunction "A_1") (pintype "unspecified"))
    )
    (net (code "68") (name "Net-(LED1-C)") (class "Default")
      (node (ref "LED1") (pin "1") (pinfunction "C_1") (pintype "input"))
      (node (ref "R1") (pin "1") (pinfunction "1_1") (pintype "input"))
    )
    (net (code "69") (name "Net-(USB1-D+)") (class "Default")
      (node (ref "R9") (pin "1") (pinfunction "1_1") (pintype "input"))
      (node (ref "USB1") (pin "3") (pinfunction "D+_3") (pintype "input"))
    )
    (net (code "70") (name "Net-(USB1-D-)") (class "Default")
      (node (ref "R8") (pin "1") (pinfunction "1_1") (pintype "input"))
      (node (ref "USB1") (pin "2") (pinfunction "D-_2") (pintype "input"))
    )
    (net (code "71") (name "VCC3V3") (class "Default")
      (node (ref "C14") (pin "2") (pinfunction "2_2") (pintype "input"))
      (node (ref "C3") (pin "2") (pinfunction "2_2") (pintype "unspecified"))
      (node (ref "C4") (pin "2") (pinfunction "2_2") (pintype "input"))
      (node (ref "CN1") (pin "1") (pinfunction "1_1") (pintype "unspecified"))
      (node (ref "CN1") (pin "2") (pinfunction "2_2") (pintype "unspecified"))
      (node (ref "D3") (pin "1") (pinfunction "A_1") (pintype "unspecified"))
      (node (ref "H1") (pin "1") (pinfunction "1_1") (pintype "unspecified"))
      (node (ref "H7") (pin "2") (pinfunction "2_2") (pintype "unspecified"))
      (node (ref "H8") (pin "5") (pinfunction "5_5") (pintype "unspecified"))
      (node (ref "H9") (pin "1") (pinfunction "1_1") (pintype "unspecified"))
      (node (ref "KEY2") (pin "1") (pinfunction "1_1") (pintype "input"))
      (node (ref "LED1") (pin "2") (pinfunction "A_2") (pintype "input"))
      (node (ref "R10") (pin "1") (pinfunction "1_1") (pintype "input"))
      (node (ref "R14") (pin "2") (pinfunction "2_2") (pintype "input"))
      (node (ref "R6") (pin "2") (pinfunction "2_2") (pintype "input"))
      (node (ref "R7") (pin "2") (pinfunction "2_2") (pintype "input"))
      (node (ref "U1") (pin "24") (pinfunction "VDD_1_24") (pintype "unspecified"))
      (node (ref "U1") (pin "36") (pinfunction "VDD_2_36") (pintype "unspecified"))
      (node (ref "U1") (pin "48") (pinfunction "VDD_3_48") (pintype "unspecified"))
      (node (ref "U1") (pin "9") (pinfunction "VDDA_9") (pintype "unspecified"))
      (node (ref "U10") (pin "1") (pinfunction "VDD_1") (pintype "unspecified"))
      (node (ref "U14") (pin "1") (pinfunction "1_1") (pintype "unspecified"))
      (node (ref "U18") (pin "1") (pinfunction "1_1") (pintype "unspecified"))
      (node (ref "U19") (pin "2") (pinfunction "2_2") (pintype "unspecified"))
      (node (ref "U2") (pin "5") (pinfunction "VOUT_5") (pintype "unspecified"))
      (node (ref "U20") (pin "2") (pinfunction "2_2") (pintype "unspecified"))
      (node (ref "U9") (pin "20") (pinfunction "VCC_20") (pintype "unspecified"))
    )
    (net (code "72") (name "VCC_BAT") (class "Default")
      (node (ref "D3") (pin "2") (pinfunction "K_2") (pintype "unspecified"))
      (node (ref "D4") (pin "2") (pinfunction "K_2") (pintype "unspecified"))
      (node (ref "U1") (pin "1") (pinfunction "VBAT_1") (pintype "unspecified"))
      (node (ref "U13") (pin "1") (pinfunction "1_1") (pintype "unspecified"))
      (node (ref "U21") (pin "1") (pinfunction "1_1") (pintype "unspecified"))
    )
    (net (code "73") (name "unconnected-(U2-NC-Pad4)") (class "Default")
      (node (ref "U2") (pin "4") (pinfunction "NC_4") (pintype "unspecified+no_connect"))
    )
    (net (code "74") (name "unconnected-(U10-NC-Pad3)") (class "Default")
      (node (ref "U10") (pin "3") (pinfunction "NC_3") (pintype "unspecified"))
    )
    (net (code "75") (name "unconnected-(USB1-EH-Pad6)") (class "Default")
      (node (ref "USB1") (pin "6") (pinfunction "EH_6") (pintype "input+no_connect"))
    )
    (net (code "76") (name "unconnected-(USB1-ID-Pad4)") (class "Default")
      (node (ref "USB1") (pin "4") (pinfunction "ID_4") (pintype "input+no_connect"))
    )
  )
)
